# 3_cyber60-mx_mcu.net
KiCad netlist of a schematic drawn in Altium Designer
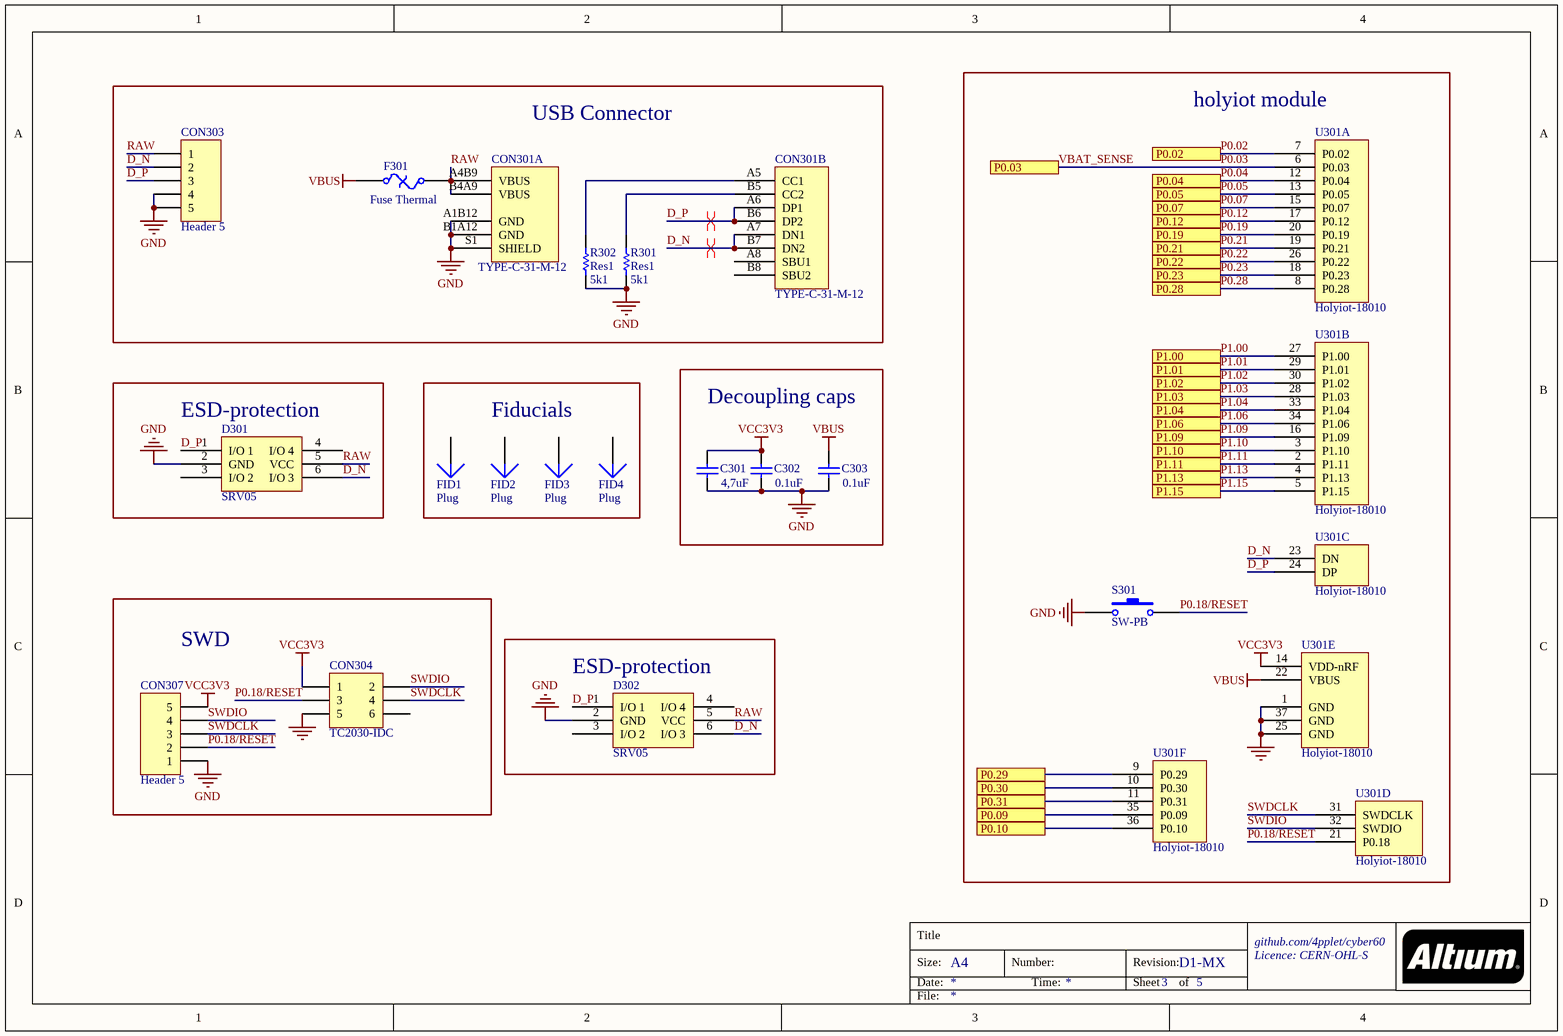
[diagram p0: 3_cyber60-mx_mcu.SchDoc]

(export (version "E")
  (design (tool "Eeschema 10.0.6"))
  (components
    (comp (ref "C301")
      (value "4,7uF")
      (footprint "C0603[1608]")
      (description "Capacitor")
      (fields (field (name "LCSC PART #") "C19666") (field (name "MRF.PART") "CL10A475KO8NNNC"))
      (libsource (lib "Miscellaneous Devices") (part "Cap"))
    )
    (comp (ref "C302")
      (value "0.1uF")
      (footprint "C0603[1608]")
      (description "Capacitor")
      (fields (field (name "MFG") "KEMET") (field (name "LCSC PART #") "C14663"))
      (libsource (lib "Miscellaneous Devices") (part "Cap"))
    )
    (comp (ref "C303")
      (value "0.1uF")
      (footprint "C0603[1608]")
      (description "Capacitor")
      (fields (field (name "MFG") "KEMET") (field (name "LCSC PART #") "C14663"))
      (libsource (lib "Miscellaneous Devices") (part "Cap"))
    )
    (comp (ref "CON301")
      (value "TYPE-C-31-M-12")
      (footprint "TYPE-C-31-M-12")
      (fields (field (name "MFG") "Korean Hroparts Elec") (field (name "LCSC PART #") "C165948"))
      (libsource (lib "Schlib1") (part "TYPE-C-31-M-12"))
    )
    (comp (ref "CON303")
      (value "Header 5")
      (footprint "JST SM04B-SRSS-TB")
      (description "JST for USB daughter board")
      (fields (field (name "MFG") "JST Sales America Inc.") (field (name "LCSC PART #") "C160404"))
      (libsource (lib "Miscellaneous Connectors") (part "Header 5"))
    )
    (comp (ref "CON304")
      (value "TC2030-IDC")
      (footprint "TC2030-IDC-NL")
      (description "Header, 3-Pin, Dual row")
      (libsource (lib "Miscellaneous Connectors") (part "Header 3X2"))
    )
    (comp (ref "CON307")
      (value "Header 5")
      (footprint "HDR1X5")
      (description "Header, 5-Pin")
      (libsource (lib "") (part "Header 5_1"))
    )
    (comp (ref "D301")
      (value "SRV05")
      (footprint "SOT-23-6")
      (fields (field (name "LCSC PART #") "C85364") (field (name "MRF.PART") "SRV05-4-P-T7"))
      (libsource (lib "Keebs") (part "SRV05"))
    )
    (comp (ref "D302")
      (value "SRV05")
      (footprint "SOT-23-6")
      (fields (field (name "LCSC PART #") "C85364") (field (name "MRF.PART") "SRV05-4-P-T7"))
      (libsource (lib "Keebs") (part "SRV05"))
    )
    (comp (ref "F301")
      (value "Fuse Thermal")
      (footprint "C1206[3216]")
      (description "Thermal Fuse")
      (fields (field (name "MFG") "Bel Fuse Inc.") (field (name "LCSC PART #") "C135338"))
      (libsource (lib "Miscellaneous Devices") (part "Fuse Thermal"))
    )
    (comp (ref "FID1")
      (value "Plug")
      (footprint "Fiducial_Nordic")
      (libsource (lib "Miscellaneous Connectors") (part "Plug"))
    )
    (comp (ref "FID2")
      (value "Plug")
      (footprint "Fiducial_Nordic")
      (libsource (lib "Miscellaneous Connectors") (part "Plug"))
    )
    (comp (ref "FID3")
      (value "Plug")
      (footprint "Fiducial_Nordic")
      (libsource (lib "Miscellaneous Connectors") (part "Plug"))
    )
    (comp (ref "FID4")
      (value "Plug")
      (footprint "Fiducial_Nordic")
      (libsource (lib "Miscellaneous Connectors") (part "Plug"))
    )
    (comp (ref "R301")
      (value "Res1")
      (footprint "R0603[1608]")
      (description "Resistor")
      (fields
        (field (name "ALTIUM_VALUE") "5k1")
        (field (name "MFG") "Panasonic Electronic Components")
        (field (name "LCSC PART #") "C23186")
      )
      (libsource (lib "Miscellaneous Devices") (part "Res1"))
    )
    (comp (ref "R302")
      (value "Res1")
      (footprint "R0603[1608]")
      (description "Resistor")
      (fields
        (field (name "ALTIUM_VALUE") "5k1")
        (field (name "MFG") "Panasonic Electronic Components")
        (field (name "LCSC PART #") "C23186")
      )
      (libsource (lib "Miscellaneous Devices") (part "Res1"))
    )
    (comp (ref "S301")
      (value "SW-PB")
      (footprint "XKB Switch")
      (description "Switch")
      (fields (field (name "MFG") "C&K") (field (name "MRF.PART") "TS-1187A-C-D-B"))
      (libsource (lib "Miscellaneous Devices") (part "SW-PB"))
    )
    (comp (ref "U301")
      (value "Holyiot-18010")
      (footprint "Holyiot-18010 - outer pads")
      (fields (field (name "MFG") "HolyIOT"))
      (libsource (lib "Keebs") (part "Holyiot-18010"))
    )
  )
  (nets
    (net (code "1") (name "/D_N") (class "Default")
      (node (ref "CON301") (pin "A7") (pinfunction "DN1_A7") (pintype "passive"))
      (node (ref "CON301") (pin "B7") (pinfunction "DN2_B7") (pintype "passive"))
      (node (ref "CON303") (pin "2") (pinfunction "2_2") (pintype "passive"))
      (node (ref "D301") (pin "6") (pinfunction "I/O_3_6") (pintype "passive"))
      (node (ref "D302") (pin "6") (pinfunction "I/O_3_6") (pintype "passive"))
      (node (ref "U301") (pin "23") (pinfunction "DN_23") (pintype "passive"))
    )
    (net (code "2") (name "/D_P") (class "Default")
      (node (ref "CON301") (pin "A6") (pinfunction "DP1_A6") (pintype "passive"))
      (node (ref "CON301") (pin "B6") (pinfunction "DP2_B6") (pintype "passive"))
      (node (ref "CON303") (pin "3") (pinfunction "3_3") (pintype "passive"))
      (node (ref "D301") (pin "1") (pinfunction "I/O_1_1") (pintype "passive"))
      (node (ref "D302") (pin "1") (pinfunction "I/O_1_1") (pintype "passive"))
      (node (ref "U301") (pin "24") (pinfunction "DP_24") (pintype "passive"))
    )
    (net (code "3") (name "/P0.02") (class "Default")
      (node (ref "U301") (pin "7") (pinfunction "P0.02_7") (pintype "passive"))
    )
    (net (code "4") (name "/P0.03") (class "Default")
      (node (ref "U301") (pin "6") (pinfunction "P0.03_6") (pintype "passive"))
    )
    (net (code "5") (name "/P0.04") (class "Default")
      (node (ref "U301") (pin "12") (pinfunction "P0.04_12") (pintype "passive"))
    )
    (net (code "6") (name "/P0.05") (class "Default")
      (node (ref "U301") (pin "13") (pinfunction "P0.05_13") (pintype "passive"))
    )
    (net (code "7") (name "/P0.07") (class "Default")
      (node (ref "U301") (pin "15") (pinfunction "P0.07_15") (pintype "passive"))
    )
    (net (code "8") (name "/P0.09") (class "Default")
      (node (ref "U301") (pin "35") (pinfunction "P0.09_35") (pintype "passive"))
    )
    (net (code "9") (name "/P0.10") (class "Default")
      (node (ref "U301") (pin "36") (pinfunction "P0.10_36") (pintype "passive"))
    )
    (net (code "10") (name "/P0.12") (class "Default")
      (node (ref "U301") (pin "17") (pinfunction "P0.12_17") (pintype "passive"))
    )
    (net (code "11") (name "/P0.18{slash}RESET") (class "Default")
      (node (ref "CON304") (pin "3") (pinfunction "3_3") (pintype "passive"))
      (node (ref "CON307") (pin "2") (pinfunction "2_2") (pintype "passive"))
      (node (ref "S301") (pin "2") (pinfunction "2_2") (pintype "passive"))
      (node (ref "U301") (pin "21") (pinfunction "P0.18_21") (pintype "passive"))
    )
    (net (code "12") (name "/P0.19") (class "Default")
      (node (ref "U301") (pin "20") (pinfunction "P0.19_20") (pintype "passive"))
    )
    (net (code "13") (name "/P0.21") (class "Default")
      (node (ref "U301") (pin "19") (pinfunction "P0.21_19") (pintype "passive"))
    )
    (net (code "14") (name "/P0.22") (class "Default")
      (node (ref "U301") (pin "26") (pinfunction "P0.22_26") (pintype "passive"))
    )
    (net (code "15") (name "/P0.23") (class "Default")
      (node (ref "U301") (pin "18") (pinfunction "P0.23_18") (pintype "passive"))
    )
    (net (code "16") (name "/P0.28") (class "Default")
      (node (ref "U301") (pin "8") (pinfunction "P0.28_8") (pintype "passive"))
    )
    (net (code "17") (name "/P0.29") (class "Default")
      (node (ref "U301") (pin "9") (pinfunction "P0.29_9") (pintype "passive"))
    )
    (net (code "18") (name "/P0.30") (class "Default")
      (node (ref "U301") (pin "10") (pinfunction "P0.30_10") (pintype "passive"))
    )
    (net (code "19") (name "/P0.31") (class "Default")
      (node (ref "U301") (pin "11") (pinfunction "P0.31_11") (pintype "passive"))
    )
    (net (code "20") (name "/P1.00") (class "Default")
      (node (ref "U301") (pin "27") (pinfunction "P1.00_27") (pintype "passive"))
    )
    (net (code "21") (name "/P1.01") (class "Default")
      (node (ref "U301") (pin "29") (pinfunction "P1.01_29") (pintype "passive"))
    )
    (net (code "22") (name "/P1.02") (class "Default")
      (node (ref "U301") (pin "30") (pinfunction "P1.02_30") (pintype "passive"))
    )
    (net (code "23") (name "/P1.03") (class "Default")
      (node (ref "U301") (pin "28") (pinfunction "P1.03_28") (pintype "passive"))
    )
    (net (code "24") (name "/P1.04") (class "Default")
      (node (ref "U301") (pin "33") (pinfunction "P1.04_33") (pintype "passive"))
    )
    (net (code "25") (name "/P1.06") (class "Default")
      (node (ref "U301") (pin "34") (pinfunction "P1.06_34") (pintype "passive"))
    )
    (net (code "26") (name "/P1.09") (class "Default")
      (node (ref "U301") (pin "16") (pinfunction "P1.09_16") (pintype "passive"))
    )
    (net (code "27") (name "/P1.10") (class "Default")
      (node (ref "U301") (pin "3") (pinfunction "P1.10_3") (pintype "passive"))
    )
    (net (code "28") (name "/P1.11") (class "Default")
      (node (ref "U301") (pin "2") (pinfunction "P1.11_2") (pintype "passive"))
    )
    (net (code "29") (name "/P1.13") (class "Default")
      (node (ref "U301") (pin "4") (pinfunction "P1.13_4") (pintype "passive"))
    )
    (net (code "30") (name "/P1.15") (class "Default")
      (node (ref "U301") (pin "5") (pinfunction "P1.15_5") (pintype "passive"))
    )
    (net (code "31") (name "/RAW") (class "Default")
      (node (ref "CON301") (pin "A4B9") (pinfunction "VBUS_A4B9") (pintype "passive"))
      (node (ref "CON301") (pin "B4A9") (pinfunction "VBUS_B4A9") (pintype "passive"))
      (node (ref "CON303") (pin "1") (pinfunction "1_1") (pintype "passive"))
      (node (ref "D301") (pin "5") (pinfunction "VCC_5") (pintype "passive"))
      (node (ref "D302") (pin "5") (pinfunction "VCC_5") (pintype "passive"))
      (node (ref "F301") (pin "2") (pinfunction "2_2") (pintype "passive"))
    )
    (net (code "32") (name "/SWDCLK") (class "Default")
      (node (ref "CON304") (pin "4") (pinfunction "4_4") (pintype "passive"))
      (node (ref "CON307") (pin "3") (pinfunction "3_3") (pintype "passive"))
      (node (ref "U301") (pin "31") (pinfunction "SWDCLK_31") (pintype "passive"))
    )
    (net (code "33") (name "/SWDIO") (class "Default")
      (node (ref "CON304") (pin "2") (pinfunction "2_2") (pintype "passive"))
      (node (ref "CON307") (pin "4") (pinfunction "4_4") (pintype "passive"))
      (node (ref "U301") (pin "32") (pinfunction "SWDIO_32") (pintype "passive"))
    )
    (net (code "34") (name "GND") (class "Default")
      (node (ref "C301") (pin "1") (pinfunction "1_1") (pintype "passive"))
      (node (ref "C302") (pin "1") (pinfunction "1_1") (pintype "passive"))
      (node (ref "C303") (pin "1") (pinfunction "1_1") (pintype "passive"))
      (node (ref "CON301") (pin "A1B12") (pinfunction "GND_A1B12") (pintype "passive"))
      (node (ref "CON301") (pin "B1A12") (pinfunction "GND_B1A12") (pintype "passive"))
      (node (ref "CON301") (pin "S1") (pinfunction "SHIELD_S1") (pintype "passive"))
      (node (ref "CON303") (pin "4") (pinfunction "4_4") (pintype "passive"))
      (node (ref "CON303") (pin "5") (pinfunction "5_5") (pintype "passive"))
      (node (ref "CON304") (pin "5") (pinfunction "5_5") (pintype "passive"))
      (node (ref "CON307") (pin "1") (pinfunction "1_1") (pintype "passive"))
      (node (ref "D301") (pin "2") (pinfunction "GND_2") (pintype "passive"))
      (node (ref "D302") (pin "2") (pinfunction "GND_2") (pintype "passive"))
      (node (ref "R301") (pin "2") (pinfunction "2_2") (pintype "passive"))
      (node (ref "R302") (pin "2") (pinfunction "2_2") (pintype "passive"))
      (node (ref "S301") (pin "1") (pinfunction "1_1") (pintype "passive"))
      (node (ref "U301") (pin "1") (pinfunction "GND_1") (pintype "passive"))
      (node (ref "U301") (pin "25") (pinfunction "GND_25") (pintype "passive"))
      (node (ref "U301") (pin "37") (pinfunction "GND_37") (pintype "passive"))
    )
    (net (code "35") (name "Net-(CON301B-CC1)") (class "Default")
      (node (ref "CON301") (pin "A5") (pinfunction "CC1_A5") (pintype "passive"))
      (node (ref "R302") (pin "1") (pinfunction "1_1") (pintype "passive"))
    )
    (net (code "36") (name "Net-(CON301B-CC2)") (class "Default")
      (node (ref "CON301") (pin "B5") (pinfunction "CC2_B5") (pintype "passive"))
      (node (ref "R301") (pin "1") (pinfunction "1_1") (pintype "passive"))
    )
    (net (code "37") (name "VBUS") (class "Default")
      (node (ref "C303") (pin "2") (pinfunction "2_2") (pintype "passive"))
      (node (ref "F301") (pin "1") (pinfunction "1_1") (pintype "passive"))
      (node (ref "U301") (pin "22") (pinfunction "VBUS_22") (pintype "passive"))
    )
    (net (code "38") (name "VCC3V3") (class "Default")
      (node (ref "C301") (pin "2") (pinfunction "2_2") (pintype "passive"))
      (node (ref "C302") (pin "2") (pinfunction "2_2") (pintype "passive"))
      (node (ref "CON304") (pin "1") (pinfunction "1_1") (pintype "passive"))
      (node (ref "CON307") (pin "5") (pinfunction "5_5") (pintype "passive"))
      (node (ref "U301") (pin "14") (pinfunction "VDD-nRF_14") (pintype "passive"))
    )
    (net (code "39") (name "unconnected-(CON301B-SBU1-PadA8)") (class "Default")
      (node (ref "CON301") (pin "A8") (pinfunction "SBU1_A8") (pintype "passive"))
    )
    (net (code "40") (name "unconnected-(CON301B-SBU2-PadB8)") (class "Default")
      (node (ref "CON301") (pin "B8") (pinfunction "SBU2_B8") (pintype "passive"))
    )
    (net (code "41") (name "unconnected-(CON304-Pad6)") (class "Default")
      (node (ref "CON304") (pin "6") (pinfunction "6_6") (pintype "passive"))
    )
    (net (code "42") (name "unconnected-(D301-I{slash}O_2-Pad3)") (class "Default")
      (node (ref "D301") (pin "3") (pinfunction "I/O_2_3") (pintype "passive"))
    )
    (net (code "43") (name "unconnected-(D301-I{slash}O_4-Pad4)") (class "Default")
      (node (ref "D301") (pin "4") (pinfunction "I/O_4_4") (pintype "passive"))
    )
    (net (code "44") (name "unconnected-(D302-I{slash}O_2-Pad3)") (class "Default")
      (node (ref "D302") (pin "3") (pinfunction "I/O_2_3") (pintype "passive"))
    )
    (net (code "45") (name "unconnected-(D302-I{slash}O_4-Pad4)") (class "Default")
      (node (ref "D302") (pin "4") (pinfunction "I/O_4_4") (pintype "passive"))
    )
    (net (code "46") (name "unconnected-(FID1-Pad1)") (class "Default")
      (node (ref "FID1") (pin "1") (pinfunction "1_1") (pintype "passive"))
    )
    (net (code "47") (name "unconnected-(FID2-Pad1)") (class "Default")
      (node (ref "FID2") (pin "1") (pinfunction "1_1") (pintype "passive"))
    )
    (net (code "48") (name "unconnected-(FID3-Pad1)") (class "Default")
      (node (ref "FID3") (pin "1") (pinfunction "1_1") (pintype "passive"))
    )
    (net (code "49") (name "unconnected-(FID4-Pad1)") (class "Default")
      (node (ref "FID4") (pin "1") (pinfunction "1_1") (pintype "passive"))
    )
  )
)
